# ProPrj_STM32__2024-12-06.net
KiCad netlist of a schematic drawn in EasyEDA Pro
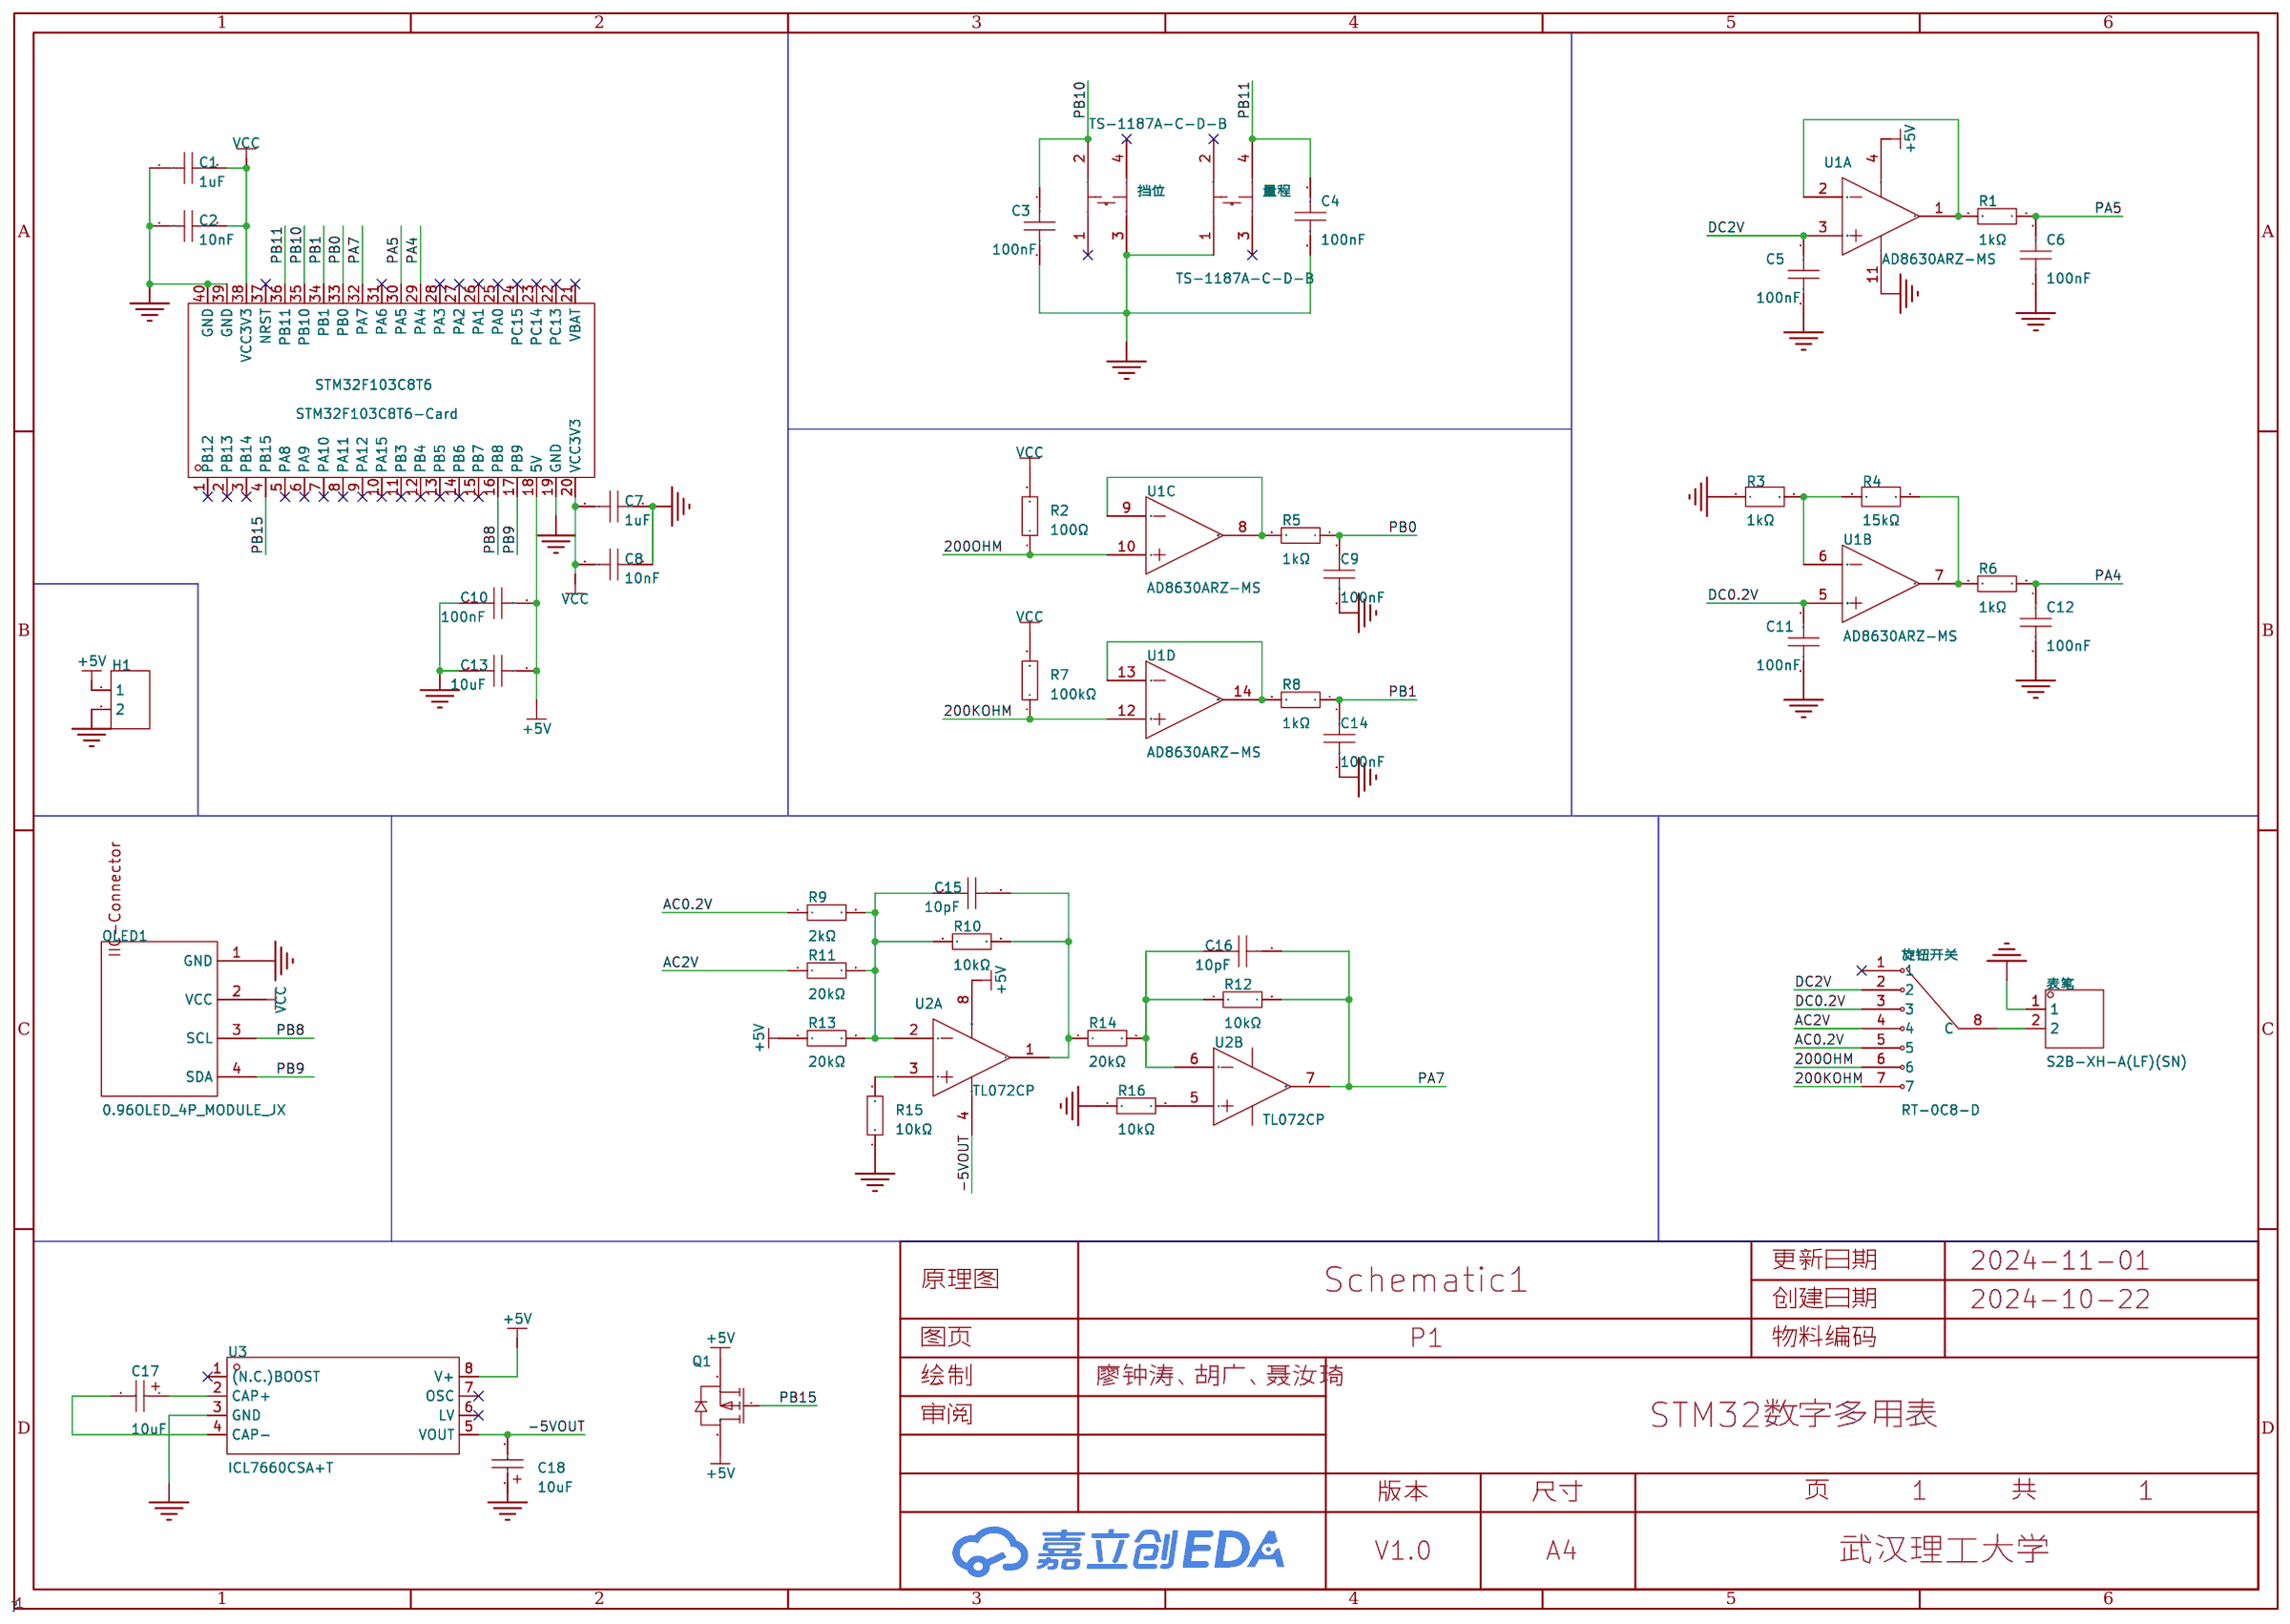
[diagram p0: schematic sheet]

(export (version "E")
  (design (tool "Eeschema 10.0.6"))
  (components
    (comp (ref "C1")
      (value "1uF")
      (footprint "easyedapro:C0603")
      (description "容值:1uF;精度:±10%;额定电压:25V;材质(温度系数):X5R;")
      (fields (field (name "Manufacturer Part") "CGA3E3X5R1E105K080AB") (field (name "Manufacturer") "TDK"))
      (libsource (lib "easyedapro") (part "CGA3E3X5R1E105K080AB"))
    )
    (comp (ref "C2")
      (value "10nF")
      (footprint "easyedapro:C0603")
      (description "容值:10nF;精度:±10%;额定电压:100V;材质(温度系数):X8R;")
      (fields (field (name "Manufacturer Part") "CGA3E2X8R2A103K080AE") (field (name "Manufacturer") "TDK"))
      (libsource (lib "easyedapro") (part "CGA3E2X8R2A103K080AE"))
    )
    (comp (ref "C3")
      (value "100nF")
      (footprint "easyedapro:C0603")
      (description "容值:100nF;精度:±20%;额定电压:25V;材质(温度系数):X8R;")
      (fields (field (name "Manufacturer Part") "CGA3E2X8R1E104M080AD") (field (name "Manufacturer") "TDK"))
      (libsource (lib "easyedapro") (part "CGA3E2X8R1E104M080AD"))
    )
    (comp (ref "C4")
      (value "100nF")
      (footprint "easyedapro:C0603")
      (description "容值:100nF;精度:±20%;额定电压:25V;材质(温度系数):X8R;")
      (fields (field (name "Manufacturer Part") "CGA3E2X8R1E104M080AD") (field (name "Manufacturer") "TDK"))
      (libsource (lib "easyedapro") (part "CGA3E2X8R1E104M080AD"))
    )
    (comp (ref "C5")
      (value "100nF")
      (footprint "easyedapro:C0603")
      (description "容值:100nF;精度:±20%;额定电压:25V;材质(温度系数):X8R;")
      (fields (field (name "Manufacturer Part") "CGA3E2X8R1E104M080AD") (field (name "Manufacturer") "TDK"))
      (libsource (lib "easyedapro") (part "CGA3E2X8R1E104M080AD"))
    )
    (comp (ref "C6")
      (value "100nF")
      (footprint "easyedapro:C0603")
      (description "容值:100nF;精度:±20%;额定电压:25V;材质(温度系数):X8R;")
      (fields (field (name "Manufacturer Part") "CGA3E2X8R1E104M080AD") (field (name "Manufacturer") "TDK"))
      (libsource (lib "easyedapro") (part "CGA3E2X8R1E104M080AD"))
    )
    (comp (ref "C7")
      (value "1uF")
      (footprint "easyedapro:C0603")
      (description "容值:1uF;精度:±10%;额定电压:25V;材质(温度系数):X5R;")
      (fields (field (name "Manufacturer Part") "CGA3E3X5R1E105K080AB") (field (name "Manufacturer") "TDK"))
      (libsource (lib "easyedapro") (part "CGA3E3X5R1E105K080AB"))
    )
    (comp (ref "C8")
      (value "10nF")
      (footprint "easyedapro:C0603")
      (description "容值:10nF;精度:±10%;额定电压:100V;材质(温度系数):X8R;")
      (fields (field (name "Manufacturer Part") "CGA3E2X8R2A103K080AE") (field (name "Manufacturer") "TDK"))
      (libsource (lib "easyedapro") (part "CGA3E2X8R2A103K080AE"))
    )
    (comp (ref "C9")
      (value "100nF")
      (footprint "easyedapro:C0603")
      (description "容值:100nF;精度:±20%;额定电压:25V;材质(温度系数):X8R;")
      (fields (field (name "Manufacturer Part") "CGA3E2X8R1E104M080AD") (field (name "Manufacturer") "TDK"))
      (libsource (lib "easyedapro") (part "CGA3E2X8R1E104M080AD"))
    )
    (comp (ref "C10")
      (value "100nF")
      (footprint "easyedapro:C0603")
      (description "容值:100nF;精度:±20%;额定电压:25V;材质(温度系数):X8R;")
      (fields (field (name "Manufacturer Part") "CGA3E2X8R1E104M080AD") (field (name "Manufacturer") "TDK"))
      (libsource (lib "easyedapro") (part "CGA3E2X8R1E104M080AD"))
    )
    (comp (ref "C11")
      (value "100nF")
      (footprint "easyedapro:C0603")
      (description "容值:100nF;精度:±20%;额定电压:25V;材质(温度系数):X8R;")
      (fields (field (name "Manufacturer Part") "CGA3E2X8R1E104M080AD") (field (name "Manufacturer") "TDK"))
      (libsource (lib "easyedapro") (part "CGA3E2X8R1E104M080AD"))
    )
    (comp (ref "C12")
      (value "100nF")
      (footprint "easyedapro:C0603")
      (description "容值:100nF;精度:±20%;额定电压:25V;材质(温度系数):X8R;")
      (fields (field (name "Manufacturer Part") "CGA3E2X8R1E104M080AD") (field (name "Manufacturer") "TDK"))
      (libsource (lib "easyedapro") (part "CGA3E2X8R1E104M080AD"))
    )
    (comp (ref "C13")
      (value "10uF")
      (footprint "easyedapro:C0603")
      (description "容值:10uF;精度:±20%;额定电压:4V;材质(温度系数):X7T;")
      (fields (field (name "Manufacturer Part") "CGA3E3X7T0G106M080AB") (field (name "Manufacturer") "TDK"))
      (libsource (lib "easyedapro") (part "CGA3E3X7T0G106M080AB"))
    )
    (comp (ref "C14")
      (value "100nF")
      (footprint "easyedapro:C0603")
      (description "容值:100nF;精度:±20%;额定电压:25V;材质(温度系数):X8R;")
      (fields (field (name "Manufacturer Part") "CGA3E2X8R1E104M080AD") (field (name "Manufacturer") "TDK"))
      (libsource (lib "easyedapro") (part "CGA3E2X8R1E104M080AD"))
    )
    (comp (ref "C15")
      (value "10pF")
      (footprint "easyedapro:C0603")
      (fields
        (field (name "Manufacturer Part") "CL10C100JB8NNNC")
        (field (name "Manufacturer") "SAMSUNG(三星)")
      )
      (libsource (lib "easyedapro") (part "CapAcitance"))
    )
    (comp (ref "C16")
      (value "10pF")
      (footprint "easyedapro:C0603")
      (fields
        (field (name "Manufacturer Part") "CL10C100JB8NNNC")
        (field (name "Manufacturer") "SAMSUNG(三星)")
      )
      (libsource (lib "easyedapro") (part "CapAcitance"))
    )
    (comp (ref "C17")
      (value "10uF")
      (footprint "easyedapro:CAP-SMD_L3.2-W1.6-RD-C7171")
      (description "容值:10uF;精度:±10%;额定电压:16V;等效串联电阻:3Ω@100kHz;")
      (fields (field (name "Manufacturer Part") "TAJA106K016RNJ") (field (name "Manufacturer") "Kyocera AVX"))
      (libsource (lib "easyedapro") (part "TAJA106K016RNJ"))
    )
    (comp (ref "C18")
      (value "10uF")
      (footprint "easyedapro:CAP-SMD_L3.2-W1.6-RD-C7171")
      (description "容值:10uF;精度:±10%;额定电压:16V;等效串联电阻:3Ω@100kHz;")
      (fields (field (name "Manufacturer Part") "TAJA106K016RNJ") (field (name "Manufacturer") "Kyocera AVX"))
      (libsource (lib "easyedapro") (part "TAJA106K016RNJ"))
    )
    (comp (ref "H1")
      (value "~")
      (footprint "easyedapro:HDR-TH_2P-P2.54-V-F")
      (libsource (lib "easyedapro") (part "Header-Female-2.54_1x2"))
    )
    (comp (ref "OLED1")
      (value "0.96OLED_4P_MODULE_JX")
      (footprint "easyedapro:0.96OLED_4P")
      (libsource (lib "easyedapro") (part "0.96oled_4p_module_jx"))
    )
    (comp (ref "Q1")
      (value "JMTL3401A")
      (footprint "easyedapro:SOT-23-3_L2.9-W1.3-P1.90-LS2.4-BR")
      (fields (field (name "Manufacturer") "JJW(捷捷微)"))
      (libsource (lib "easyedapro") (part "JMTL3401A"))
    )
    (comp (ref "R1")
      (value "1kΩ")
      (footprint "easyedapro:R0603")
      (description "电阻类型:厚膜电阻;阻值:1kΩ;精度:±1%;功率:100mW;最大工作电压:75V;温度系数:±100ppm/°C;")
      (fields
        (field (name "Manufacturer Part") "0603WAF1001T5E")
        (field (name "Manufacturer") "UNI-ROYAL(厚声)")
      )
      (libsource (lib "easyedapro") (part "0603WAF1001T5E"))
    )
    (comp (ref "R2")
      (value "100Ω")
      (footprint "easyedapro:R0603")
      (description "阻值:100Ω;精度:±5%;功率:100mW;")
      (fields (field (name "Manufacturer Part") "RMC06031005%N") (field (name "Manufacturer") "Tyohm(幸亚电阻)"))
      (libsource (lib "easyedapro") (part "RMC06031005%N"))
    )
    (comp (ref "R3")
      (value "1kΩ")
      (footprint "easyedapro:R0603")
      (description "电阻类型:薄膜电阻;阻值:1kΩ;精度:±0.1%;功率:125mW;最大工作电压:75V;温度系数:±25ppm/°C;")
      (fields
        (field (name "Manufacturer Part") "TNPW06031K00BEEA")
        (field (name "Manufacturer") "VISHAY(威世)")
      )
      (libsource (lib "easyedapro") (part "TNPW06031K00BEEA"))
    )
    (comp (ref "R4")
      (value "15kΩ")
      (footprint "easyedapro:R0603")
      (description "电阻类型:厚膜电阻;阻值:15kΩ;精度:±5%;功率:100mW;最大工作电压:75V;温度系数:±200ppm/°C;")
      (fields
        (field (name "Manufacturer Part") "CRCW060315K0JNEA")
        (field (name "Manufacturer") "VISHAY(威世)")
      )
      (libsource (lib "easyedapro") (part "CRCW060315K0JNEA"))
    )
    (comp (ref "R5")
      (value "1kΩ")
      (footprint "easyedapro:R0603")
      (description "电阻类型:厚膜电阻;阻值:1kΩ;精度:±1%;功率:100mW;最大工作电压:75V;温度系数:±100ppm/°C;")
      (fields
        (field (name "Manufacturer Part") "0603WAF1001T5E")
        (field (name "Manufacturer") "UNI-ROYAL(厚声)")
      )
      (libsource (lib "easyedapro") (part "0603WAF1001T5E"))
    )
    (comp (ref "R6")
      (value "1kΩ")
      (footprint "easyedapro:R0603")
      (description "电阻类型:厚膜电阻;阻值:1kΩ;精度:±1%;功率:100mW;最大工作电压:75V;温度系数:±100ppm/°C;")
      (fields
        (field (name "Manufacturer Part") "0603WAF1001T5E")
        (field (name "Manufacturer") "UNI-ROYAL(厚声)")
      )
      (libsource (lib "easyedapro") (part "0603WAF1001T5E"))
    )
    (comp (ref "R7")
      (value "100kΩ")
      (footprint "easyedapro:R0603")
      (description "阻值:150kΩ;精度:±1%;功率:100mW;")
      (fields
        (field (name "Manufacturer Part") "0603WAF1003T5E")
        (field (name "Manufacturer") "UNI-ROYAL(厚声)")
      )
      (libsource (lib "easyedapro") (part "RMC0603150K1%N"))
    )
    (comp (ref "R8")
      (value "1kΩ")
      (footprint "easyedapro:R0603")
      (description "电阻类型:厚膜电阻;阻值:1kΩ;精度:±1%;功率:100mW;最大工作电压:75V;温度系数:±100ppm/°C;")
      (fields
        (field (name "Manufacturer Part") "0603WAF1001T5E")
        (field (name "Manufacturer") "UNI-ROYAL(厚声)")
      )
      (libsource (lib "easyedapro") (part "0603WAF1001T5E"))
    )
    (comp (ref "R9")
      (value "2kΩ")
      (footprint "easyedapro:R0603")
      (fields
        (field (name "Manufacturer Part") "0603WAF2001T5E")
        (field (name "Manufacturer") "UNI-ROYAL(厚声)")
      )
      (libsource (lib "easyedapro") (part "电阻"))
    )
    (comp (ref "R10")
      (value "10kΩ")
      (footprint "easyedapro:R0603")
      (fields
        (field (name "Manufacturer Part") "0603WAF1002T5E")
        (field (name "Manufacturer") "UNI-ROYAL(厚声)")
      )
      (libsource (lib "easyedapro") (part "电阻"))
    )
    (comp (ref "R11")
      (value "20kΩ")
      (footprint "easyedapro:R0603")
      (fields
        (field (name "Manufacturer Part") "0603WAF2002T5E")
        (field (name "Manufacturer") "UNI-ROYAL(厚声)")
      )
      (libsource (lib "easyedapro") (part "电阻"))
    )
    (comp (ref "R12")
      (value "10kΩ")
      (footprint "easyedapro:R0603")
      (fields
        (field (name "Manufacturer Part") "0603WAF1002T5E")
        (field (name "Manufacturer") "UNI-ROYAL(厚声)")
      )
      (libsource (lib "easyedapro") (part "电阻"))
    )
    (comp (ref "R13")
      (value "20kΩ")
      (footprint "easyedapro:R0603")
      (fields
        (field (name "Manufacturer Part") "0603WAF2002T5E")
        (field (name "Manufacturer") "UNI-ROYAL(厚声)")
      )
      (libsource (lib "easyedapro") (part "电阻"))
    )
    (comp (ref "R14")
      (value "20kΩ")
      (footprint "easyedapro:R0603")
      (fields
        (field (name "Manufacturer Part") "0603WAF2002T5E")
        (field (name "Manufacturer") "UNI-ROYAL(厚声)")
      )
      (libsource (lib "easyedapro") (part "电阻"))
    )
    (comp (ref "R15")
      (value "10kΩ")
      (footprint "easyedapro:R0603")
      (fields
        (field (name "Manufacturer Part") "0603WAF1002T5E")
        (field (name "Manufacturer") "UNI-ROYAL(厚声)")
      )
      (libsource (lib "easyedapro") (part "电阻"))
    )
    (comp (ref "R16")
      (value "10kΩ")
      (footprint "easyedapro:R0603")
      (fields
        (field (name "Manufacturer Part") "0603WAF1002T5E")
        (field (name "Manufacturer") "UNI-ROYAL(厚声)")
      )
      (libsource (lib "easyedapro") (part "电阻"))
    )
    (comp (ref "STM32F103C8T6")
      (value "STM32F103C8T6-Card")
      (footprint "easyedapro:CONN-TH_L53.3-W22.9_STM32F103C8T6-CARD")
      (libsource (lib "easyedapro") (part "STM32F103C8T6-CARD"))
    )
    (comp (ref "U1")
      (value "AD8630ARZ-MS")
      (footprint "easyedapro:SOIC-14_L8.7-W3.9-P1.27-LS6.0-BL")
      (fields (field (name "Manufacturer") "MSKSEMI(美森科)"))
      (libsource (lib "easyedapro") (part "AD8630ARZ-MS"))
    )
    (comp (ref "U2")
      (value "TL072CP")
      (footprint "easyedapro:DIP-8_L9.6-W6.4-P2.54-LS7.6-BL-1")
      (description "运放类型:J-FET;放大器组数:2;增益带宽积（GBP）:3MHz;压摆率（SR）:13 V/us;电源电压:7V~36V,±3.5V~18V;各通道供电电流:1.4mA;")
      (fields (field (name "Manufacturer") "TI(德州仪器)"))
      (libsource (lib "easyedapro") (part "TL072CP"))
    )
    (comp (ref "U3")
      (value "ICL7660CSA+T")
      (footprint "easyedapro:SO-8_L4.9-W3.9-P1.27-LS5.9-BL")
      (description "开关电容电压转换器、20mA电荷泵，采用工业标准引脚排列")
      (fields (field (name "Manufacturer") "ADI(亚德诺)/MAXIM(美信)"))
      (libsource (lib "easyedapro") (part "ICL7660CSA+T"))
    )
    (comp (ref "挡位")
      (value "TS-1187A-C-D-B")
      (footprint "easyedapro:KEY-SMD_4P-L5.2-W5.2-P3.7-LS6.4-TL")
      (fields (field (name "Manufacturer") "XKB Connectivity(中国星坤)"))
      (libsource (lib "easyedapro") (part "TS-1187A-C-D-B"))
    )
    (comp (ref "旋钮开关")
      (value "RT-0C8-D")
      (footprint "easyedapro:SW-TH_RT-0C4-D")
      (description "带灯:-;接点数:-;触点类型:-;额定电流:500mA;额定电压(AC):-;额定电压(DC):24V;切换角度:-;层数:-;每层极数:-;")
      (fields (field (name "Manufacturer") "Dailywell(德利威)"))
      (libsource (lib "easyedapro") (part "RT-0C8-D"))
    )
    (comp (ref "表笔")
      (value "S2B-XH-A(LF)(SN)")
      (footprint "easyedapro:CONN-TH_S2B-XH-A-LF-SN")
      (fields (field (name "Manufacturer") "JST"))
      (libsource (lib "easyedapro") (part "s2b-xh-a-(lf)(sn)"))
    )
    (comp (ref "量程")
      (value "TS-1187A-C-D-B")
      (footprint "easyedapro:KEY-SMD_4P-L5.2-W5.2-P3.7-LS6.4-TL")
      (fields (field (name "Manufacturer") "XKB Connectivity(中国星坤)"))
      (libsource (lib "easyedapro") (part "TS-1187A-C-D-B"))
    )
  )
  (nets
    (net (code "1") (name "+5V") (class "Default")
      (node (ref "C10") (pin "2") (pinfunction "2_2") (pintype "unspecified"))
      (node (ref "C13") (pin "1") (pinfunction "1_1") (pintype "unspecified"))
      (node (ref "H1") (pin "1") (pinfunction "1_1") (pintype "input"))
      (node (ref "Q1") (pin "2") (pinfunction "S_2") (pintype "input"))
      (node (ref "Q1") (pin "3") (pinfunction "D_3") (pintype "input"))
      (node (ref "R13") (pin "1") (pinfunction "1_1") (pintype "input"))
      (node (ref "STM32F103C8T6") (pin "18") (pinfunction "5V_18") (pintype "unspecified"))
      (node (ref "U1") (pin "4") (pinfunction "V+_4") (pintype "unspecified"))
      (node (ref "U2") (pin "8") (pinfunction "VCC+_8") (pintype "unspecified"))
      (node (ref "U3") (pin "8") (pinfunction "V+_8") (pintype "unspecified"))
    )
    (net (code "2") (name "/-5VOUT") (class "Default")
      (node (ref "C18") (pin "2") (pinfunction "2_2") (pintype "input"))
      (node (ref "U2") (pin "4") (pinfunction "VCC-_4") (pintype "unspecified"))
      (node (ref "U3") (pin "5") (pinfunction "VOUT_5") (pintype "unspecified"))
    )
    (net (code "3") (name "/200KOHM") (class "Default")
      (node (ref "R7") (pin "1") (pinfunction "1_1") (pintype "unspecified"))
      (node (ref "U1") (pin "12") (pinfunction "+IN_D_12") (pintype "unspecified"))
      (node (ref "旋钮开关") (pin "7") (pinfunction "7_7") (pintype "unspecified"))
    )
    (net (code "4") (name "/200OHM") (class "Default")
      (node (ref "R2") (pin "1") (pinfunction "1_1") (pintype "unspecified"))
      (node (ref "U1") (pin "10") (pinfunction "+IN_C_10") (pintype "unspecified"))
      (node (ref "旋钮开关") (pin "6") (pinfunction "6_6") (pintype "unspecified"))
    )
    (net (code "5") (name "/AC0.2V") (class "Default")
      (node (ref "R9") (pin "1") (pinfunction "1_1") (pintype "input"))
      (node (ref "旋钮开关") (pin "5") (pinfunction "5_5") (pintype "unspecified"))
    )
    (net (code "6") (name "/AC2V") (class "Default")
      (node (ref "R11") (pin "1") (pinfunction "1_1") (pintype "input"))
      (node (ref "旋钮开关") (pin "4") (pinfunction "4_4") (pintype "unspecified"))
    )
    (net (code "7") (name "/DC0.2V") (class "Default")
      (node (ref "C11") (pin "1") (pinfunction "1_1") (pintype "unspecified"))
      (node (ref "U1") (pin "5") (pinfunction "+IN_B_5") (pintype "unspecified"))
      (node (ref "旋钮开关") (pin "3") (pinfunction "3_3") (pintype "unspecified"))
    )
    (net (code "8") (name "/DC2V") (class "Default")
      (node (ref "C5") (pin "1") (pinfunction "1_1") (pintype "unspecified"))
      (node (ref "U1") (pin "3") (pinfunction "+IN_A_3") (pintype "unspecified"))
      (node (ref "旋钮开关") (pin "2") (pinfunction "2_2") (pintype "unspecified"))
    )
    (net (code "9") (name "/PA4") (class "Default")
      (node (ref "C12") (pin "1") (pinfunction "1_1") (pintype "unspecified"))
      (node (ref "R6") (pin "2") (pinfunction "2_2") (pintype "input"))
      (node (ref "STM32F103C8T6") (pin "29") (pinfunction "PA4_29") (pintype "unspecified"))
    )
    (net (code "10") (name "/PA5") (class "Default")
      (node (ref "C6") (pin "2") (pinfunction "2_2") (pintype "unspecified"))
      (node (ref "R1") (pin "1") (pinfunction "1_1") (pintype "input"))
      (node (ref "STM32F103C8T6") (pin "30") (pinfunction "PA5_30") (pintype "unspecified"))
    )
    (net (code "11") (name "/PA7") (class "Default")
      (node (ref "C16") (pin "2") (pinfunction "2_2") (pintype "input"))
      (node (ref "R12") (pin "2") (pinfunction "2_2") (pintype "input"))
      (node (ref "STM32F103C8T6") (pin "32") (pinfunction "PA7_32") (pintype "unspecified"))
      (node (ref "U2") (pin "7") (pinfunction "OUT2_7") (pintype "output"))
    )
    (net (code "12") (name "/PB0") (class "Default")
      (node (ref "C9") (pin "1") (pinfunction "1_1") (pintype "unspecified"))
      (node (ref "R5") (pin "1") (pinfunction "1_1") (pintype "input"))
      (node (ref "STM32F103C8T6") (pin "33") (pinfunction "PB0_33") (pintype "unspecified"))
    )
    (net (code "13") (name "/PB1") (class "Default")
      (node (ref "C14") (pin "1") (pinfunction "1_1") (pintype "unspecified"))
      (node (ref "R8") (pin "1") (pinfunction "1_1") (pintype "input"))
      (node (ref "STM32F103C8T6") (pin "34") (pinfunction "PB1_34") (pintype "unspecified"))
    )
    (net (code "14") (name "/PB8") (class "Default")
      (node (ref "OLED1") (pin "3") (pinfunction "SCL_3") (pintype "unspecified"))
      (node (ref "STM32F103C8T6") (pin "16") (pinfunction "PB8_16") (pintype "unspecified"))
    )
    (net (code "15") (name "/PB9") (class "Default")
      (node (ref "OLED1") (pin "4") (pinfunction "SDA_4") (pintype "unspecified"))
      (node (ref "STM32F103C8T6") (pin "17") (pinfunction "PB9_17") (pintype "unspecified"))
    )
    (net (code "16") (name "/PB10") (class "Default")
      (node (ref "C3") (pin "1") (pinfunction "1_1") (pintype "unspecified"))
      (node (ref "STM32F103C8T6") (pin "35") (pinfunction "PB10_35") (pintype "unspecified"))
      (node (ref "挡位") (pin "2") (pinfunction "2_2") (pintype "input"))
    )
    (net (code "17") (name "/PB11") (class "Default")
      (node (ref "C4") (pin "1") (pinfunction "1_1") (pintype "unspecified"))
      (node (ref "STM32F103C8T6") (pin "36") (pinfunction "PB11_36") (pintype "unspecified"))
      (node (ref "量程") (pin "4") (pinfunction "4_4") (pintype "input"))
    )
    (net (code "18") (name "/PB15") (class "Default")
      (node (ref "Q1") (pin "1") (pinfunction "G_1") (pintype "input"))
      (node (ref "STM32F103C8T6") (pin "4") (pinfunction "PB15_4") (pintype "unspecified"))
    )
    (net (code "19") (name "GND") (class "Default")
      (node (ref "C1") (pin "1") (pinfunction "1_1") (pintype "unspecified"))
      (node (ref "C10") (pin "1") (pinfunction "1_1") (pintype "unspecified"))
      (node (ref "C11") (pin "2") (pinfunction "2_2") (pintype "unspecified"))
      (node (ref "C12") (pin "2") (pinfunction "2_2") (pintype "unspecified"))
      (node (ref "C13") (pin "2") (pinfunction "2_2") (pintype "unspecified"))
      (node (ref "C14") (pin "2") (pinfunction "2_2") (pintype "unspecified"))
      (node (ref "C18") (pin "1") (pinfunction "1_1") (pintype "input"))
      (node (ref "C2") (pin "1") (pinfunction "1_1") (pintype "unspecified"))
      (node (ref "C3") (pin "2") (pinfunction "2_2") (pintype "unspecified"))
      (node (ref "C4") (pin "2") (pinfunction "2_2") (pintype "unspecified"))
      (node (ref "C5") (pin "2") (pinfunction "2_2") (pintype "unspecified"))
      (node (ref "C6") (pin "1") (pinfunction "1_1") (pintype "unspecified"))
      (node (ref "C7") (pin "2") (pinfunction "2_2") (pintype "unspecified"))
      (node (ref "C8") (pin "2") (pinfunction "2_2") (pintype "unspecified"))
      (node (ref "C9") (pin "2") (pinfunction "2_2") (pintype "unspecified"))
      (node (ref "H1") (pin "2") (pinfunction "2_2") (pintype "input"))
      (node (ref "OLED1") (pin "1") (pinfunction "GND_1") (pintype "unspecified"))
      (node (ref "R15") (pin "1") (pinfunction "1_1") (pintype "input"))
      (node (ref "R16") (pin "1") (pinfunction "1_1") (pintype "input"))
      (node (ref "R3") (pin "1") (pinfunction "1_1") (pintype "unspecified"))
      (node (ref "STM32F103C8T6") (pin "19") (pinfunction "GND_19") (pintype "unspecified"))
      (node (ref "STM32F103C8T6") (pin "39") (pinfunction "GND_39") (pintype "unspecified"))
      (node (ref "STM32F103C8T6") (pin "40") (pinfunction "GND_40") (pintype "unspecified"))
      (node (ref "U1") (pin "11") (pinfunction "V-_11") (pintype "unspecified"))
      (node (ref "U3") (pin "3") (pinfunction "GND_3") (pintype "unspecified"))
      (node (ref "挡位") (pin "3") (pinfunction "3_3") (pintype "input"))
      (node (ref "表笔") (pin "1") (pinfunction "1_1") (pintype "unspecified"))
      (node (ref "量程") (pin "1") (pinfunction "1_1") (pintype "input"))
    )
    (net (code "20") (name "Net-(U1A-OUTA)") (class "Default")
      (node (ref "R1") (pin "2") (pinfunction "2_2") (pintype "input"))
      (node (ref "U1") (pin "1") (pinfunction "OUTA_1") (pintype "output"))
      (node (ref "U1") (pin "2") (pinfunction "–IN_A_2") (pintype "unspecified"))
    )
    (net (code "21") (name "Net-(U1B-OUTB)") (class "Default")
      (node (ref "R4") (pin "2") (pinfunction "2_2") (pintype "input"))
      (node (ref "R6") (pin "1") (pinfunction "1_1") (pintype "input"))
      (node (ref "U1") (pin "7") (pinfunction "OUTB_7") (pintype "output"))
    )
    (net (code "22") (name "Net-(U1B-–IN_B)") (class "Default")
      (node (ref "R3") (pin "2") (pinfunction "2_2") (pintype "unspecified"))
      (node (ref "R4") (pin "1") (pinfunction "1_1") (pintype "input"))
      (node (ref "U1") (pin "6") (pinfunction "–IN_B_6") (pintype "unspecified"))
    )
    (net (code "23") (name "Net-(U1C-OUTC)") (class "Default")
      (node (ref "R5") (pin "2") (pinfunction "2_2") (pintype "input"))
      (node (ref "U1") (pin "8") (pinfunction "OUTC_8") (pintype "output"))
      (node (ref "U1") (pin "9") (pinfunction "–IN_C_9") (pintype "unspecified"))
    )
    (net (code "24") (name "Net-(U1D-OUTD)") (class "Default")
      (node (ref "R8") (pin "2") (pinfunction "2_2") (pintype "input"))
      (node (ref "U1") (pin "13") (pinfunction "–IN_D_13") (pintype "unspecified"))
      (node (ref "U1") (pin "14") (pinfunction "OUTD_14") (pintype "output"))
    )
    (net (code "25") (name "Net-(U2A-IN1+)") (class "Default")
      (node (ref "R15") (pin "2") (pinfunction "2_2") (pintype "input"))
      (node (ref "U2") (pin "3") (pinfunction "IN1+_3") (pintype "unspecified"))
    )
    (net (code "26") (name "Net-(U2A-IN1-)") (class "Default")
      (node (ref "C15") (pin "1") (pinfunction "1_1") (pintype "input"))
      (node (ref "R10") (pin "1") (pinfunction "1_1") (pintype "input"))
      (node (ref "R11") (pin "2") (pinfunction "2_2") (pintype "input"))
      (node (ref "R13") (pin "2") (pinfunction "2_2") (pintype "input"))
      (node (ref "R9") (pin "2") (pinfunction "2_2") (pintype "input"))
      (node (ref "U2") (pin "2") (pinfunction "IN1-_2") (pintype "unspecified"))
    )
    (net (code "27") (name "Net-(U2A-OUT1)") (class "Default")
      (node (ref "C15") (pin "2") (pinfunction "2_2") (pintype "input"))
      (node (ref "R10") (pin "2") (pinfunction "2_2") (pintype "input"))
      (node (ref "R14") (pin "1") (pinfunction "1_1") (pintype "input"))
      (node (ref "U2") (pin "1") (pinfunction "OUT1_1") (pintype "output"))
    )
    (net (code "28") (name "Net-(U2B-IN2+)") (class "Default")
      (node (ref "R16") (pin "2") (pinfunction "2_2") (pintype "input"))
      (node (ref "U2") (pin "5") (pinfunction "IN2+_5") (pintype "unspecified"))
    )
    (net (code "29") (name "Net-(U2B-IN2-)") (class "Default")
      (node (ref "C16") (pin "1") (pinfunction "1_1") (pintype "input"))
      (node (ref "R12") (pin "1") (pinfunction "1_1") (pintype "input"))
      (node (ref "R14") (pin "2") (pinfunction "2_2") (pintype "input"))
      (node (ref "U2") (pin "6") (pinfunction "IN2-_6") (pintype "unspecified"))
    )
    (net (code "30") (name "Net-(U3-CAP+)") (class "Default")
      (node (ref "C17") (pin "1") (pinfunction "1_1") (pintype "input"))
      (node (ref "U3") (pin "2") (pinfunction "CAP+_2") (pintype "unspecified"))
    )
    (net (code "31") (name "Net-(U3-CAP-)") (class "Default")
      (node (ref "C17") (pin "2") (pinfunction "2_2") (pintype "input"))
      (node (ref "U3") (pin "4") (pinfunction "CAP-_4") (pintype "unspecified"))
    )
    (net (code "32") (name "Net-(旋钮开关-C)") (class "Default")
      (node (ref "旋钮开关") (pin "8") (pinfunction "C_8") (pintype "unspecified"))
      (node (ref "表笔") (pin "2") (pinfunction "2_2") (pintype "unspecified"))
    )
    (net (code "33") (name "VCC") (class "Default")
      (node (ref "C1") (pin "2") (pinfunction "2_2") (pintype "unspecified"))
      (node (ref "C2") (pin "2") (pinfunction "2_2") (pintype "unspecified"))
      (node (ref "C7") (pin "1") (pinfunction "1_1") (pintype "unspecified"))
      (node (ref "C8") (pin "1") (pinfunction "1_1") (pintype "unspecified"))
      (node (ref "OLED1") (pin "2") (pinfunction "VCC_2") (pintype "unspecified"))
      (node (ref "R2") (pin "2") (pinfunction "2_2") (pintype "unspecified"))
      (node (ref "R7") (pin "2") (pinfunction "2_2") (pintype "unspecified"))
      (node (ref "STM32F103C8T6") (pin "20") (pinfunction "VCC3V3_20") (pintype "unspecified"))
      (node (ref "STM32F103C8T6") (pin "38") (pinfunction "VCC3V3_38") (pintype "unspecified"))
    )
    (net (code "34") (name "unconnected-(STM32F103C8T6-NRST-Pad37)") (class "Default")
      (node (ref "STM32F103C8T6") (pin "37") (pinfunction "NRST_37") (pintype "unspecified+no_connect"))
    )
    (net (code "35") (name "unconnected-(STM32F103C8T6-PA0-Pad25)") (class "Default")
      (node (ref "STM32F103C8T6") (pin "25") (pinfunction "PA0_25") (pintype "unspecified+no_connect"))
    )
    (net (code "36") (name "unconnected-(STM32F103C8T6-PA1-Pad26)") (class "Default")
      (node (ref "STM32F103C8T6") (pin "26") (pinfunction "PA1_26") (pintype "unspecified+no_connect"))
    )
    (net (code "37") (name "unconnected-(STM32F103C8T6-PA2-Pad27)") (class "Default")
      (node (ref "STM32F103C8T6") (pin "27") (pinfunction "PA2_27") (pintype "unspecified+no_connect"))
    )
    (net (code "38") (name "unconnected-(STM32F103C8T6-PA3-Pad28)") (class "Default")
      (node (ref "STM32F103C8T6") (pin "28") (pinfunction "PA3_28") (pintype "unspecified+no_connect"))
    )
    (net (code "39") (name "unconnected-(STM32F103C8T6-PA6-Pad31)") (class "Default")
      (node (ref "STM32F103C8T6") (pin "31") (pinfunction "PA6_31") (pintype "unspecified+no_connect"))
    )
    (net (code "40") (name "unconnected-(STM32F103C8T6-PA8-Pad5)") (class "Default")
      (node (ref "STM32F103C8T6") (pin "5") (pinfunction "PA8_5") (pintype "unspecified+no_connect"))
    )
    (net (code "41") (name "unconnected-(STM32F103C8T6-PA9-Pad6)") (class "Default")
      (node (ref "STM32F103C8T6") (pin "6") (pinfunction "PA9_6") (pintype "unspecified+no_connect"))
    )
    (net (code "42") (name "unconnected-(STM32F103C8T6-PA10-Pad7)") (class "Default")
      (node (ref "STM32F103C8T6") (pin "7") (pinfunction "PA10_7") (pintype "unspecified+no_connect"))
    )
    (net (code "43") (name "unconnected-(STM32F103C8T6-PA11-Pad8)") (class "Default")
      (node (ref "STM32F103C8T6") (pin "8") (pinfunction "PA11_8") (pintype "unspecified+no_connect"))
    )
    (net (code "44") (name "unconnected-(STM32F103C8T6-PA12-Pad9)") (class "Default")
      (node (ref "STM32F103C8T6") (pin "9") (pinfunction "PA12_9") (pintype "unspecified+no_connect"))
    )
    (net (code "45") (name "unconnected-(STM32F103C8T6-PA15-Pad10)") (class "Default")
      (node (ref "STM32F103C8T6") (pin "10") (pinfunction "PA15_10") (pintype "unspecified+no_connect"))
    )
    (net (code "46") (name "unconnected-(STM32F103C8T6-PB3-Pad11)") (class "Default")
      (node (ref "STM32F103C8T6") (pin "11") (pinfunction "PB3_11") (pintype "unspecified+no_connect"))
    )
    (net (code "47") (name "unconnected-(STM32F103C8T6-PB4-Pad12)") (class "Default")
      (node (ref "STM32F103C8T6") (pin "12") (pinfunction "PB4_12") (pintype "unspecified+no_connect"))
    )
    (net (code "48") (name "unconnected-(STM32F103C8T6-PB5-Pad13)") (class "Default")
      (node (ref "STM32F103C8T6") (pin "13") (pinfunction "PB5_13") (pintype "unspecified+no_connect"))
    )
    (net (code "49") (name "unconnected-(STM32F103C8T6-PB6-Pad14)") (class "Default")
      (node (ref "STM32F103C8T6") (pin "14") (pinfunction "PB6_14") (pintype "unspecified+no_connect"))
    )
    (net (code "50") (name "unconnected-(STM32F103C8T6-PB7-Pad15)") (class "Default")
      (node (ref "STM32F103C8T6") (pin "15") (pinfunction "PB7_15") (pintype "unspecified+no_connect"))
    )
    (net (code "51") (name "unconnected-(STM32F103C8T6-PB12-Pad1)") (class "Default")
      (node (ref "STM32F103C8T6") (pin "1") (pinfunction "PB12_1") (pintype "unspecified+no_connect"))
    )
    (net (code "52") (name "unconnected-(STM32F103C8T6-PB13-Pad2)") (class "Default")
      (node (ref "STM32F103C8T6") (pin "2") (pinfunction "PB13_2") (pintype "unspecified+no_connect"))
    )
    (net (code "53") (name "unconnected-(STM32F103C8T6-PB14-Pad3)") (class "Default")
      (node (ref "STM32F103C8T6") (pin "3") (pinfunction "PB14_3") (pintype "unspecified+no_connect"))
    )
    (net (code "54") (name "unconnected-(STM32F103C8T6-PC13-Pad22)") (class "Default")
      (node (ref "STM32F103C8T6") (pin "22") (pinfunction "PC13_22") (pintype "unspecified+no_connect"))
    )
    (net (code "55") (name "unconnected-(STM32F103C8T6-PC14-Pad23)") (class "Default")
      (node (ref "STM32F103C8T6") (pin "23") (pinfunction "PC14_23") (pintype "unspecified+no_connect"))
    )
    (net (code "56") (name "unconnected-(STM32F103C8T6-PC15-Pad24)") (class "Default")
      (node (ref "STM32F103C8T6") (pin "24") (pinfunction "PC15_24") (pintype "unspecified+no_connect"))
    )
    (net (code "57") (name "unconnected-(STM32F103C8T6-VBAT-Pad21)") (class "Default")
      (node (ref "STM32F103C8T6") (pin "21") (pinfunction "VBAT_21") (pintype "unspecified+no_connect"))
    )
    (net (code "58") (name "unconnected-(U3-(N.C.)BOOST-Pad1)") (class "Default")
      (node (ref "U3") (pin "1") (pinfunction "(N.C.)BOOST_1") (pintype "unspecified+no_connect"))
    )
    (net (code "59") (name "unconnected-(U3-LV-Pad6)") (class "Default")
      (node (ref "U3") (pin "6") (pinfunction "LV_6") (pintype "unspecified+no_connect"))
    )
    (net (code "60") (name "unconnected-(U3-OSC-Pad7)") (class "Default")
      (node (ref "U3") (pin "7") (pinfunction "OSC_7") (pintype "unspecified+no_connect"))
    )
    (net (code "61") (name "unconnected-(挡位-Pad1)") (class "Default")
      (node (ref "挡位") (pin "1") (pinfunction "1_1") (pintype "input+no_connect"))
    )
    (net (code "62") (name "unconnected-(挡位-Pad4)") (class "Default")
      (node (ref "挡位") (pin "4") (pinfunction "4_4") (pintype "input+no_connect"))
    )
    (net (code "63") (name "unconnected-(旋钮开关-Pad1)") (class "Default")
      (node (ref "旋钮开关") (pin "1") (pinfunction "1_1") (pintype "unspecified+no_connect"))
    )
    (net (code "64") (name "unconnected-(量程-Pad2)") (class "Default")
      (node (ref "量程") (pin "2") (pinfunction "2_2") (pintype "input+no_connect"))
    )
    (net (code "65") (name "unconnected-(量程-Pad3)") (class "Default")
      (node (ref "量程") (pin "3") (pinfunction "3_3") (pintype "input+no_connect"))
    )
  )
)
